# PERfECT-PRO-1.net
KiCad netlist of a schematic drawn in Altium Designer
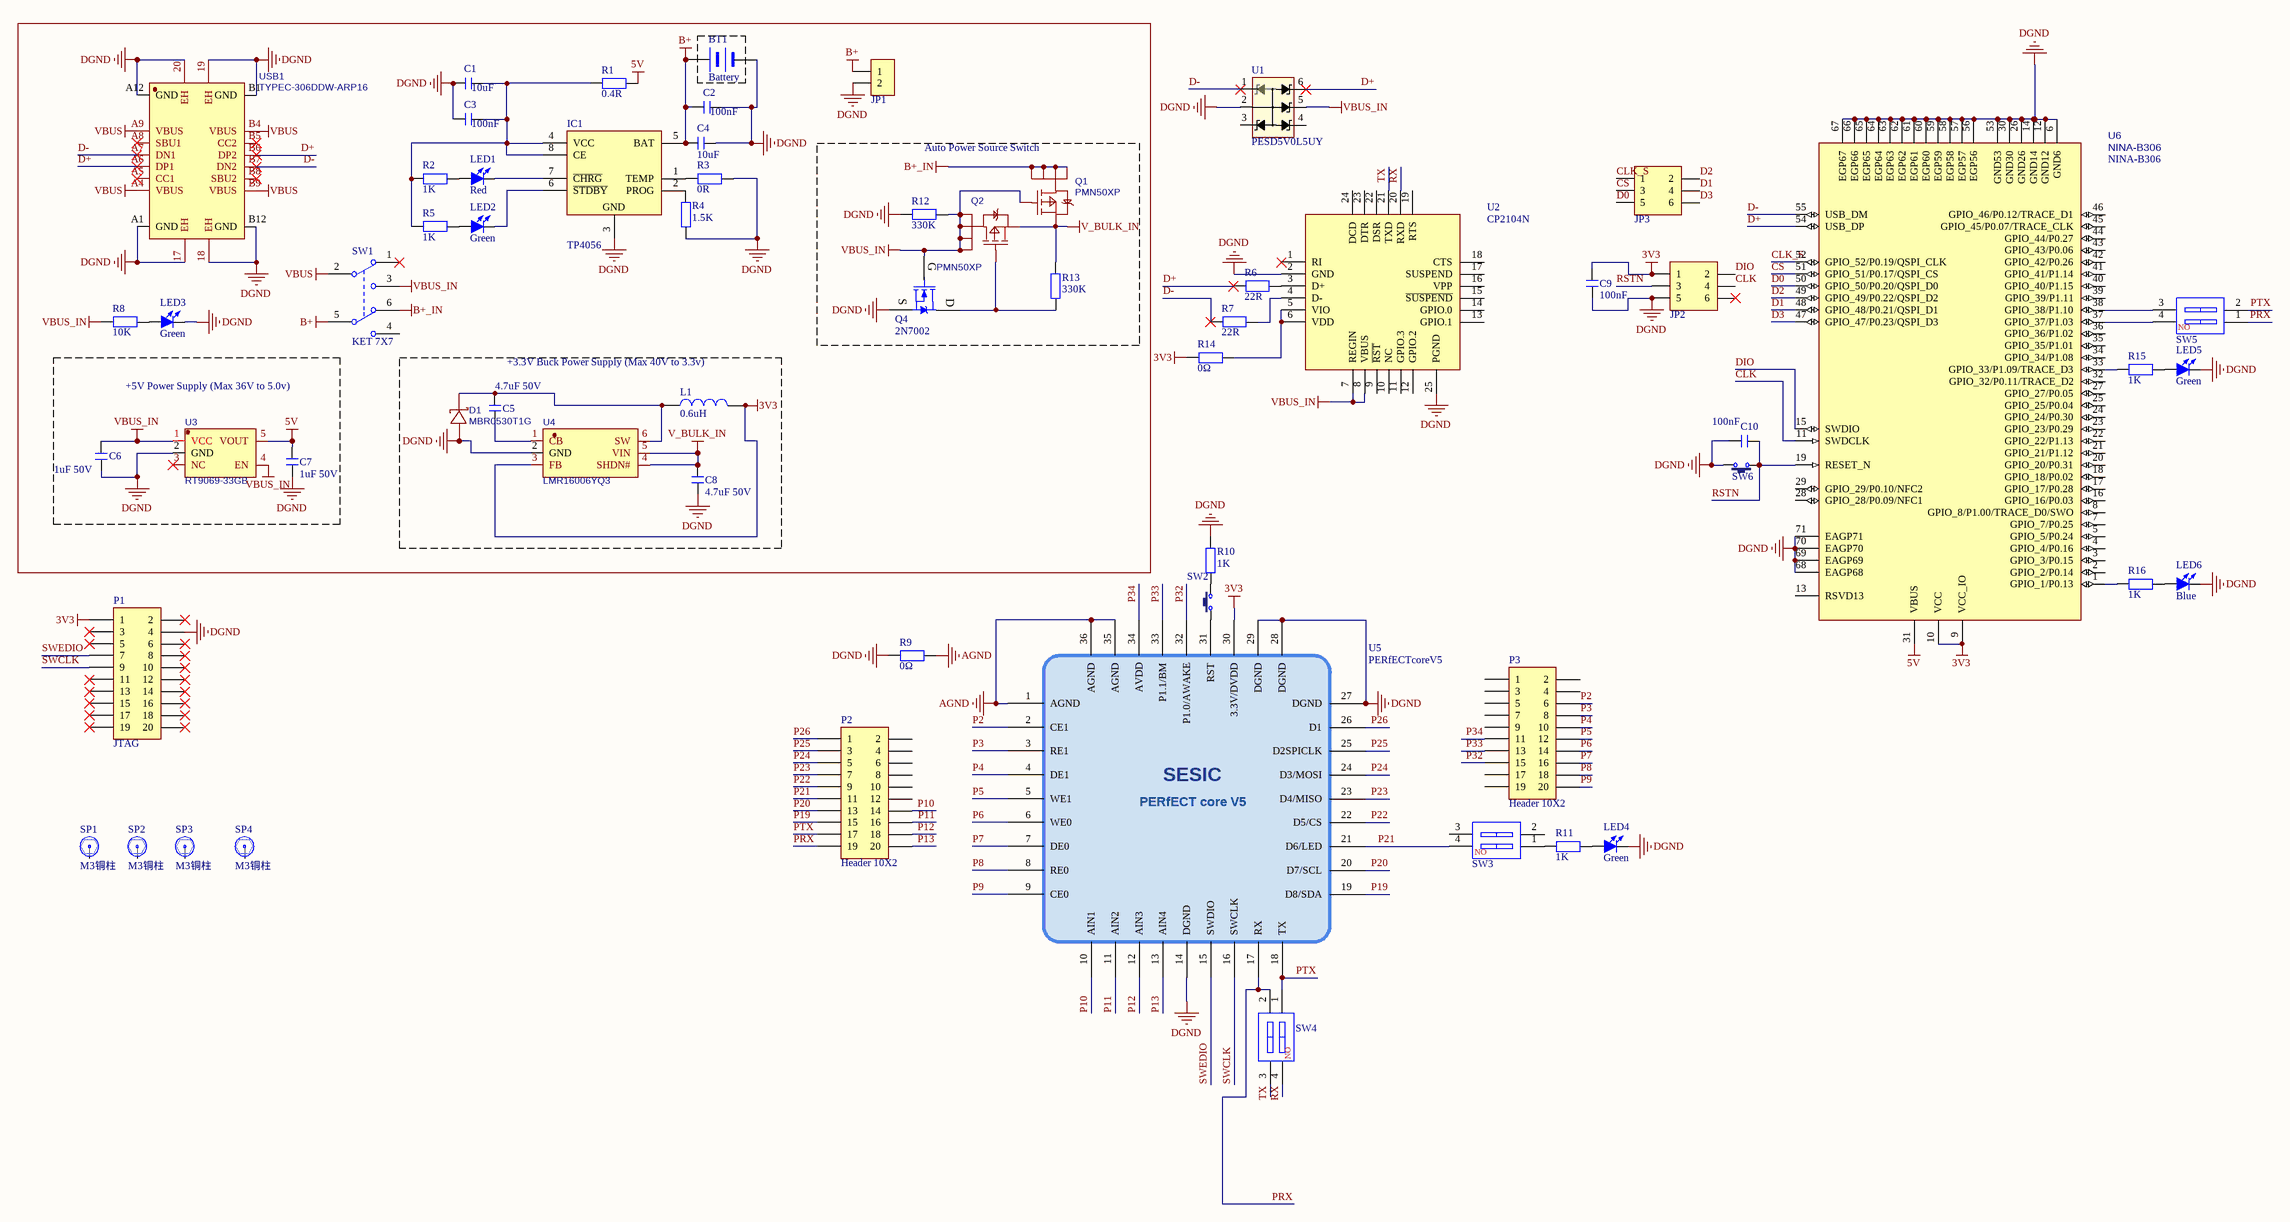
[diagram p0: PERfECT-PRO-1.SchDoc]

(export (version "E")
  (design (tool "Eeschema 10.0.6"))
  (components
    (comp (ref "BT1") (value "Battery") (libsource (lib "电池及电源") (part "干电池")))
    (comp (ref "C1")
      (value "10uF")
      (footprint "C 0603_L")
      (description "无极性贴片电容")
      (fields (field (name "版权归属") "源创客"))
      (libsource (lib "3.1   - 电阻-电容-电感") (part "C"))
    )
    (comp (ref "C2")
      (value "100nF")
      (footprint "C 0603_L")
      (description "无极性贴片电容")
      (fields (field (name "版权归属") "源创客"))
      (libsource (lib "3.1   - 电阻-电容-电感") (part "C"))
    )
    (comp (ref "C3")
      (value "100nF")
      (footprint "C 0603_L")
      (description "无极性贴片电容")
      (fields (field (name "版权归属") "源创客"))
      (libsource (lib "3.1   - 电阻-电容-电感") (part "C"))
    )
    (comp (ref "C4")
      (value "10uF")
      (footprint "C 0603_L")
      (description "无极性贴片电容")
      (fields (field (name "版权归属") "源创客"))
      (libsource (lib "3.1   - 电阻-电容-电感") (part "C"))
    )
    (comp (ref "C5")
      (value "4.7uF 50V")
      (footprint "C 0603_L")
      (description "无极性贴片电容")
      (fields (field (name "版权归属") "源创客"))
      (libsource (lib "3.1   - 电阻-电容-电感") (part "C"))
    )
    (comp (ref "C6")
      (value "1uF 50V")
      (footprint "C 0603_L")
      (description "无极性贴片电容")
      (fields (field (name "版权归属") "源创客"))
      (libsource (lib "3.1   - 电阻-电容-电感") (part "C"))
    )
    (comp (ref "C7")
      (value "1uF 50V")
      (footprint "C 0603_L")
      (description "无极性贴片电容")
      (fields (field (name "版权归属") "源创客"))
      (libsource (lib "3.1   - 电阻-电容-电感") (part "C"))
    )
    (comp (ref "C8")
      (value "4.7uF 50V")
      (footprint "C 0603_L")
      (description "无极性贴片电容")
      (fields (field (name "版权归属") "源创客"))
      (libsource (lib "3.1   - 电阻-电容-电感") (part "C"))
    )
    (comp (ref "C9")
      (value "100nF")
      (footprint "C 0603_L")
      (description "无极性贴片电容")
      (fields (field (name "版权归属") "源创客"))
      (libsource (lib "3.1   - 电阻-电容-电感") (part "C"))
    )
    (comp (ref "C10")
      (value "100nF")
      (footprint "C 0603_L")
      (description "无极性贴片电容")
      (fields (field (name "版权归属") "源创客"))
      (libsource (lib "3.1   - 电阻-电容-电感") (part "C"))
    )
    (comp (ref "D1")
      (value "MBR0530T1G")
      (footprint "MBR0530T1G")
      (fields (field (name "BOM_SUPPLIER PART") "C82046"))
      (libsource (lib "PERfECT-PRO") (part "MBR0530T1G"))
    )
    (comp (ref "IC1")
      (value "TP4056")
      (footprint "SOP8_N")
      (description "锂电池充电管理")
      (fields (field (name "版权归属") "源创客"))
      (libsource (lib "1.3   - 电源类芯片") (part "TP4056"))
    )
    (comp (ref "JP1")
      (value "HDR-1X2")
      (footprint "XH2.54-LI-2P")
      (description "2P接插件")
      (fields (field (name "版权归属") "源创客"))
      (libsource (lib "4.5   - 接插件-脚距2.54") (part "Header 2"))
    )
    (comp (ref "JP2")
      (value "Header3X2")
      (footprint "HDR2.54-LI-2x3P")
      (description "3*2P接插件")
      (fields (field (name "版权归属") "源创客"))
      (libsource (lib "4.5   - 接插件-脚距2.54") (part "Header 3X2"))
    )
    (comp (ref "JP3")
      (value "Header3X2")
      (footprint "HDR2.54-LI-2x3P")
      (description "3*2P接插件")
      (fields (field (name "版权归属") "源创客"))
      (libsource (lib "4.5   - 接插件-脚距2.54") (part "Header 3X2"))
    )
    (comp (ref "L1")
      (value "0.6uH")
      (footprint "L 1206")
      (description "小功率贴片电感")
      (fields (field (name "版权归属") "源创客"))
      (libsource (lib "3.1   - 电阻-电容-电感") (part "L"))
    )
    (comp (ref "LED1")
      (value "Red")
      (footprint "LED 0603R")
      (description "贴片LED")
      (fields (field (name "版权归属") "源创客"))
      (libsource (lib "9.1   - LED") (part "LED-SMD"))
    )
    (comp (ref "LED2")
      (value "Green")
      (footprint "LED 0603R")
      (description "贴片LED")
      (fields (field (name "版权归属") "源创客"))
      (libsource (lib "9.1   - LED") (part "LED-SMD"))
    )
    (comp (ref "LED3")
      (value "Green")
      (footprint "LED 0603R")
      (description "贴片LED")
      (fields (field (name "版权归属") "源创客"))
      (libsource (lib "9.1   - LED") (part "LED-SMD"))
    )
    (comp (ref "LED4")
      (value "Green")
      (footprint "LED 0603R")
      (description "贴片LED")
      (fields (field (name "版权归属") "源创客"))
      (libsource (lib "9.1   - LED") (part "LED-SMD"))
    )
    (comp (ref "LED5")
      (value "Green")
      (footprint "LED 0603R")
      (description "贴片LED")
      (fields (field (name "版权归属") "源创客"))
      (libsource (lib "9.1   - LED") (part "LED-SMD"))
    )
    (comp (ref "LED6")
      (value "Blue")
      (footprint "LED 0603R")
      (description "贴片LED")
      (fields (field (name "版权归属") "源创客"))
      (libsource (lib "9.1   - LED") (part "LED-SMD"))
    )
    (comp (ref "P1")
      (value "JTAG")
      (footprint "HDR2X10")
      (description "Header, 10-Pin, Dual row")
      (fields (field (name "PUBLISHER") "Altium Limited"))
      (libsource (lib "PERfECT-PRO") (part "Header 10X2"))
    )
    (comp (ref "P2")
      (value "Header 10X2")
      (footprint "HDR2X10")
      (description "Header, 10-Pin, Dual row")
      (fields (field (name "PUBLISHER") "Altium Limited"))
      (libsource (lib "PERfECT-PRO") (part "Header 10X2"))
    )
    (comp (ref "P3")
      (value "Header 10X2")
      (footprint "HDR2X10")
      (description "Header, 10-Pin, Dual row")
      (fields (field (name "PUBLISHER") "Altium Limited"))
      (libsource (lib "PERfECT-PRO") (part "Header 10X2"))
    )
    (comp (ref "Q1")
      (value "PMN50XP")
      (footprint "PMN50XP:PMN50XP")
      (fields (field (name "BOM_SUPPLIER PART") "C558228") (field (name "CONTRIBUTOR") "LCSC"))
      (libsource (lib "PERfECT-PRO-LIB") (part "PMN50XP"))
    )
    (comp (ref "Q2")
      (value "PMN50XP")
      (footprint "PMN50XP:PMN50XP")
      (fields (field (name "BOM_SUPPLIER PART") "C558228") (field (name "CONTRIBUTOR") "LCSC"))
      (libsource (lib "PERfECT-PRO-LIB") (part "PMN50XP"))
    )
    (comp (ref "Q4")
      (value "2N7002")
      (footprint "SOT23-3N")
      (description "N沟道场效应管")
      (fields (field (name "版权归属") "源创客"))
      (libsource (lib "6.1   - 场效应管-可控硅") (part "SI2302"))
    )
    (comp (ref "R1")
      (value "0.4R")
      (footprint "R 0603_L")
      (description "贴片电阻")
      (fields (field (name "版权归属") "源创客"))
      (libsource (lib "3.1   - 电阻-电容-电感") (part "R"))
    )
    (comp (ref "R2")
      (value "1K")
      (footprint "R 0603_L")
      (description "贴片电阻")
      (fields (field (name "版权归属") "源创客"))
      (libsource (lib "3.1   - 电阻-电容-电感") (part "R"))
    )
    (comp (ref "R3")
      (value "0R")
      (footprint "R 0603_L")
      (description "贴片电阻")
      (fields (field (name "版权归属") "源创客"))
      (libsource (lib "3.1   - 电阻-电容-电感") (part "R"))
    )
    (comp (ref "R4")
      (value "1.5K")
      (footprint "R 0603_L")
      (description "贴片电阻")
      (fields (field (name "版权归属") "源创客"))
      (libsource (lib "3.1   - 电阻-电容-电感") (part "R"))
    )
    (comp (ref "R5")
      (value "1K")
      (footprint "R 0603_L")
      (description "贴片电阻")
      (fields (field (name "版权归属") "源创客"))
      (libsource (lib "3.1   - 电阻-电容-电感") (part "R"))
    )
    (comp (ref "R6")
      (value "22R")
      (footprint "R 0603_L")
      (description "贴片电阻")
      (fields (field (name "版权归属") "源创客"))
      (libsource (lib "3.1   - 电阻-电容-电感") (part "R"))
    )
    (comp (ref "R7")
      (value "22R")
      (footprint "R 0603_L")
      (description "贴片电阻")
      (fields (field (name "版权归属") "源创客"))
      (libsource (lib "3.1   - 电阻-电容-电感") (part "R"))
    )
    (comp (ref "R8")
      (value "10K")
      (footprint "R 0603_L")
      (description "贴片电阻")
      (fields (field (name "版权归属") "源创客"))
      (libsource (lib "3.1   - 电阻-电容-电感") (part "R"))
    )
    (comp (ref "R9")
      (value "0Ω")
      (footprint "R 0603_L")
      (description "贴片电阻")
      (fields (field (name "版权归属") "源创客"))
      (libsource (lib "3.1   - 电阻-电容-电感") (part "R"))
    )
    (comp (ref "R10")
      (value "1K")
      (footprint "R 0603_L")
      (description "贴片电阻")
      (fields (field (name "版权归属") "源创客"))
      (libsource (lib "3.1   - 电阻-电容-电感") (part "R"))
    )
    (comp (ref "R11")
      (value "1K")
      (footprint "R 0603_L")
      (description "贴片电阻")
      (fields (field (name "版权归属") "源创客"))
      (libsource (lib "3.1   - 电阻-电容-电感") (part "R"))
    )
    (comp (ref "R12")
      (value "330K")
      (footprint "R 0603_L")
      (description "贴片电阻")
      (fields (field (name "版权归属") "源创客"))
      (libsource (lib "3.1   - 电阻-电容-电感") (part "R"))
    )
    (comp (ref "R13")
      (value "330K")
      (footprint "R 0603_L")
      (description "贴片电阻")
      (fields (field (name "版权归属") "源创客"))
      (libsource (lib "3.1   - 电阻-电容-电感") (part "R"))
    )
    (comp (ref "R14")
      (value "0Ω")
      (footprint "R 0603_L")
      (description "贴片电阻")
      (fields (field (name "版权归属") "源创客"))
      (libsource (lib "3.1   - 电阻-电容-电感") (part "R"))
    )
    (comp (ref "R15")
      (value "1K")
      (footprint "R 0603_L")
      (description "贴片电阻")
      (fields (field (name "版权归属") "源创客"))
      (libsource (lib "3.1   - 电阻-电容-电感") (part "R"))
    )
    (comp (ref "R16")
      (value "1K")
      (footprint "R 0603_L")
      (description "贴片电阻")
      (fields (field (name "版权归属") "源创客"))
      (libsource (lib "3.1   - 电阻-电容-电感") (part "R"))
    )
    (comp (ref "SP1")
      (value "M3铜柱")
      (footprint "M3x4_L")
      (description "铜柱")
      (fields (field (name "版权归属") "源创客"))
      (libsource (lib "15.1 - 未分类器件") (part "铜柱小焊盘"))
    )
    (comp (ref "SP2")
      (value "M3铜柱")
      (footprint "M3x4_L")
      (description "铜柱")
      (fields (field (name "版权归属") "源创客"))
      (libsource (lib "15.1 - 未分类器件") (part "铜柱小焊盘"))
    )
    (comp (ref "SP3")
      (value "M3铜柱")
      (footprint "M3x4_L")
      (description "铜柱")
      (fields (field (name "版权归属") "源创客"))
      (libsource (lib "15.1 - 未分类器件") (part "铜柱小焊盘"))
    )
    (comp (ref "SP4")
      (value "M3铜柱")
      (footprint "M3x4_L")
      (description "铜柱")
      (fields (field (name "版权归属") "源创客"))
      (libsource (lib "15.1 - 未分类器件") (part "铜柱小焊盘"))
    )
    (comp (ref "SW1")
      (value "KET 7X7")
      (footprint "KFT DIP-7X7")
      (description "7*7自锁开关")
      (fields (field (name "版权归属") "源创客"))
      (libsource (lib "5.1   - 按键-开关") (part "KET 7X7"))
    )
    (comp (ref "SW2")
      (value "3x6x5")
      (footprint "TSW SMD-3*6*2.5")
      (description "3x6轻触开关")
      (fields (field (name "版权归属") "源创客"))
      (libsource (lib "5.1   - 按键-开关") (part "TSW 3x6"))
    )
    (comp (ref "SW3")
      (value "CSW-2P")
      (footprint "CSW1.27 SMD-2P")
      (description "2路编码开关")
      (fields (field (name "版权归属") "源创客"))
      (libsource (lib "5.1   - 按键-开关") (part "CSW-2P"))
    )
    (comp (ref "SW4")
      (value "CSW-2P")
      (footprint "CSW1.27 SMD-2P")
      (description "2路编码开关")
      (fields (field (name "版权归属") "源创客"))
      (libsource (lib "5.1   - 按键-开关") (part "CSW-2P"))
    )
    (comp (ref "SW5")
      (value "CSW-2P")
      (footprint "CSW1.27 SMD-2P")
      (description "2路编码开关")
      (fields (field (name "版权归属") "源创客"))
      (libsource (lib "5.1   - 按键-开关") (part "CSW-2P"))
    )
    (comp (ref "SW6")
      (value "3x6x5")
      (footprint "TSW SMD-3*6*2.5")
      (description "3x6轻触开关")
      (fields (field (name "版权归属") "源创客"))
      (libsource (lib "") (part "TSW 3x6_1"))
    )
    (comp (ref "U1")
      (value "PESD5V0L5UY")
      (footprint "SOT65P210X110-6N")
      (description "TVS SOT-363 RoHS")
      (fields (field (name "MANUFACTURER") "Yenji") (field (name "PARTNUMBER") "PESD5V0L5UY"))
      (libsource (lib "PERfECT-PRO") (part "PESD5V0L5UY"))
    )
    (comp (ref "U2")
      (value "CP2104N")
      (footprint "24-QFN")
      (description "IC BRIDGE USB TO UART 24QFN")
      (fields (field (name "MANUFACTURER") "Silicon Labs") (field (name "PARTNUMBER") "C47742"))
      (libsource (lib "PERfECT-PRO") (part "CP2104N"))
    )
    (comp (ref "U3")
      (value "RT9069-33GB")
      (footprint "SOT-23-5_L3.0-W1.7-P0.95-LS2.8-BR")
      (fields (field (name "BOM_SUPPLIER PART") "C147969") (field (name "CONTRIBUTOR") "LCSC"))
      (libsource (lib "PERfECT-PRO") (part "RT9069-33GB"))
    )
    (comp (ref "U4")
      (value "LMR16006YQ3")
      (footprint "LMR16006YQ3")
      (fields
        (field (name "BOM_SUPPLIER PART") "C290195")
        (field (name "BOM_MANUFACTURER PART") "LMR16006YDDCR")
        (field (name "CONTRIBUTOR") "LCSC")
      )
      (libsource (lib "PERfECT-PRO") (part "LMR16006YQ3"))
    )
    (comp (ref "U5")
      (value "PERfECTcoreV5")
      (footprint "PERfECTcore36")
      (description "This is the 5th version of PERfEC core.https://github.com/WISE-PERfECT/PERfECT")
      (libsource (lib "PERfECT-PRO") (part "PERfECTcoreV5"))
    )
    (comp (ref "U6")
      (value "NINA-B306")
      (footprint "NINA_LGA71R_1500X1000X223_PCB")
      (description "u-blox NINA-B306 Bluetooth 5 LE, 802.15.4 module")
      (fields (field (name "MANUFACTURER") "u-blox") (field (name "ALTIUM_VALUE") "NINA-B306"))
      (libsource (lib "PERfECT-PRO") (part "NINA-B306"))
    )
    (comp (ref "USB1")
      (value "TYPEC-306DDW-ARP16")
      (footprint "USBC_DIP")
      (fields (field (name "BOM_SUPPLIER PART") "C2840393") (field (name "CONTRIBUTOR") "LCSC"))
      (libsource (lib "PERfECT-PRO") (part "TYPEC-306DDW-ARP16"))
    )
  )
  (nets
    (net (code "1") (name "/CLK") (class "Default")
      (node (ref "JP2") (pin "4") (pinfunction "4_4") (pintype "passive"))
      (node (ref "U6") (pin "11") (pinfunction "SWDCLK_11") (pintype "input"))
    )
    (net (code "2") (name "/CLK_S") (class "Default")
      (node (ref "JP3") (pin "1") (pinfunction "1_1") (pintype "passive"))
      (node (ref "U6") (pin "52") (pinfunction "GPIO_52/P0.19/QSPI_CLK_52") (pintype "bidirectional"))
    )
    (net (code "3") (name "/CS") (class "Default")
      (node (ref "JP3") (pin "3") (pinfunction "3_3") (pintype "passive"))
      (node (ref "U6") (pin "51") (pinfunction "GPIO_51/P0.17/QSPI_CS_51") (pintype "bidirectional"))
    )
    (net (code "4") (name "/D+") (class "Default")
      (node (ref "R6") (pin "1") (pinfunction "1_1") (pintype "passive"))
      (node (ref "U1") (pin "6") (pinfunction "6_6") (pintype "passive"))
      (node (ref "U6") (pin "54") (pinfunction "USB_DP_54") (pintype "bidirectional"))
      (node (ref "USB1") (pin "A6") (pinfunction "DP1_A6") (pintype "passive"))
      (node (ref "USB1") (pin "B6") (pinfunction "DP2_B6") (pintype "passive"))
    )
    (net (code "5") (name "/D-") (class "Default")
      (node (ref "R7") (pin "1") (pinfunction "1_1") (pintype "passive"))
      (node (ref "U1") (pin "1") (pinfunction "1_1") (pintype "passive"))
      (node (ref "U6") (pin "55") (pinfunction "USB_DM_55") (pintype "bidirectional"))
      (node (ref "USB1") (pin "A7") (pinfunction "DN1_A7") (pintype "passive"))
      (node (ref "USB1") (pin "B7") (pinfunction "DN2_B7") (pintype "passive"))
    )
    (net (code "6") (name "/D0") (class "Default")
      (node (ref "JP3") (pin "5") (pinfunction "5_5") (pintype "passive"))
      (node (ref "U6") (pin "50") (pinfunction "GPIO_50/P0.20/QSPI_D0_50") (pintype "bidirectional"))
    )
    (net (code "7") (name "/D1") (class "Default")
      (node (ref "JP3") (pin "4") (pinfunction "4_4") (pintype "passive"))
      (node (ref "U6") (pin "48") (pinfunction "GPIO_48/P0.21/QSPI_D1_48") (pintype "bidirectional"))
    )
    (net (code "8") (name "/D2") (class "Default")
      (node (ref "JP3") (pin "2") (pinfunction "2_2") (pintype "passive"))
      (node (ref "U6") (pin "49") (pinfunction "GPIO_49/P0.22/QSPI_D2_49") (pintype "bidirectional"))
    )
    (net (code "9") (name "/D3") (class "Default")
      (node (ref "JP3") (pin "6") (pinfunction "6_6") (pintype "passive"))
      (node (ref "U6") (pin "47") (pinfunction "GPIO_47/P0.23/QSPI_D3_47") (pintype "bidirectional"))
    )
    (net (code "10") (name "/DIO") (class "Default")
      (node (ref "JP2") (pin "2") (pinfunction "2_2") (pintype "passive"))
      (node (ref "U6") (pin "15") (pinfunction "SWDIO_15") (pintype "bidirectional"))
    )
    (net (code "11") (name "/P2") (class "Default")
      (node (ref "P3") (pin "6") (pinfunction "6_6") (pintype "passive"))
      (node (ref "U5") (pin "2") (pinfunction "CE1_2") (pintype "passive"))
    )
    (net (code "12") (name "/P3") (class "Default")
      (node (ref "P3") (pin "8") (pinfunction "8_8") (pintype "passive"))
      (node (ref "U5") (pin "3") (pinfunction "RE1_3") (pintype "passive"))
    )
    (net (code "13") (name "/P4") (class "Default")
      (node (ref "P3") (pin "10") (pinfunction "10_10") (pintype "passive"))
      (node (ref "U5") (pin "4") (pinfunction "DE1_4") (pintype "passive"))
    )
    (net (code "14") (name "/P5") (class "Default")
      (node (ref "P3") (pin "12") (pinfunction "12_12") (pintype "passive"))
      (node (ref "U5") (pin "5") (pinfunction "WE1_5") (pintype "passive"))
    )
    (net (code "15") (name "/P6") (class "Default")
      (node (ref "P3") (pin "14") (pinfunction "14_14") (pintype "passive"))
      (node (ref "U5") (pin "6") (pinfunction "WE0_6") (pintype "passive"))
    )
    (net (code "16") (name "/P7") (class "Default")
      (node (ref "P3") (pin "16") (pinfunction "16_16") (pintype "passive"))
      (node (ref "U5") (pin "7") (pinfunction "DE0_7") (pintype "passive"))
    )
    (net (code "17") (name "/P8") (class "Default")
      (node (ref "P3") (pin "18") (pinfunction "18_18") (pintype "passive"))
      (node (ref "U5") (pin "8") (pinfunction "RE0_8") (pintype "passive"))
    )
    (net (code "18") (name "/P9") (class "Default")
      (node (ref "P3") (pin "20") (pinfunction "20_20") (pintype "passive"))
      (node (ref "U5") (pin "9") (pinfunction "CE0_9") (pintype "passive"))
    )
    (net (code "19") (name "/P10") (class "Default")
      (node (ref "P2") (pin "14") (pinfunction "14_14") (pintype "passive"))
      (node (ref "U5") (pin "10") (pinfunction "AIN1_10") (pintype "passive"))
    )
    (net (code "20") (name "/P11") (class "Default")
      (node (ref "P2") (pin "16") (pinfunction "16_16") (pintype "passive"))
      (node (ref "U5") (pin "11") (pinfunction "AIN2_11") (pintype "passive"))
    )
    (net (code "21") (name "/P12") (class "Default")
      (node (ref "P2") (pin "18") (pinfunction "18_18") (pintype "passive"))
      (node (ref "U5") (pin "12") (pinfunction "AIN3_12") (pintype "passive"))
    )
    (net (code "22") (name "/P13") (class "Default")
      (node (ref "P2") (pin "20") (pinfunction "20_20") (pintype "passive"))
      (node (ref "U5") (pin "13") (pinfunction "AIN4_13") (pintype "passive"))
    )
    (net (code "23") (name "/P19") (class "Default")
      (node (ref "P2") (pin "15") (pinfunction "15_15") (pintype "passive"))
      (node (ref "U5") (pin "19") (pinfunction "D8/SDA_19") (pintype "passive"))
    )
    (net (code "24") (name "/P20") (class "Default")
      (node (ref "P2") (pin "13") (pinfunction "13_13") (pintype "passive"))
      (node (ref "U5") (pin "20") (pinfunction "D7/SCL_20") (pintype "passive"))
    )
    (net (code "25") (name "/P21") (class "Default")
      (node (ref "P2") (pin "11") (pinfunction "11_11") (pintype "passive"))
      (node (ref "SW3") (pin "4") (pinfunction "4_4") (pintype "passive"))
      (node (ref "U5") (pin "21") (pinfunction "D6/LED_21") (pintype "passive"))
    )
    (net (code "26") (name "/P22") (class "Default")
      (node (ref "P2") (pin "9") (pinfunction "9_9") (pintype "passive"))
      (node (ref "U5") (pin "22") (pinfunction "D5/CS_22") (pintype "passive"))
    )
    (net (code "27") (name "/P23") (class "Default")
      (node (ref "P2") (pin "7") (pinfunction "7_7") (pintype "passive"))
      (node (ref "U5") (pin "23") (pinfunction "D4/MISO_23") (pintype "passive"))
    )
    (net (code "28") (name "/P24") (class "Default")
      (node (ref "P2") (pin "5") (pinfunction "5_5") (pintype "passive"))
      (node (ref "U5") (pin "24") (pinfunction "D3/MOSI_24") (pintype "passive"))
    )
    (net (code "29") (name "/P25") (class "Default")
      (node (ref "P2") (pin "3") (pinfunction "3_3") (pintype "passive"))
      (node (ref "U5") (pin "25") (pinfunction "D2SPICLK_25") (pintype "passive"))
    )
    (net (code "30") (name "/P26") (class "Default")
      (node (ref "P2") (pin "1") (pinfunction "1_1") (pintype "passive"))
      (node (ref "U5") (pin "26") (pinfunction "D1_26") (pintype "passive"))
    )
    (net (code "31") (name "/P32") (class "Default")
      (node (ref "P3") (pin "15") (pinfunction "15_15") (pintype "passive"))
      (node (ref "U5") (pin "32") (pinfunction "P1.0/AWAKE_32") (pintype "passive"))
    )
    (net (code "32") (name "/P33") (class "Default")
      (node (ref "P3") (pin "13") (pinfunction "13_13") (pintype "passive"))
      (node (ref "U5") (pin "33") (pinfunction "P1.1/BM_33") (pintype "passive"))
    )
    (net (code "33") (name "/P34") (class "Default")
      (node (ref "P3") (pin "11") (pinfunction "11_11") (pintype "passive"))
      (node (ref "U5") (pin "34") (pinfunction "AVDD_34") (pintype "passive"))
    )
    (net (code "34") (name "/PRX") (class "Default")
      (node (ref "P2") (pin "19") (pinfunction "19_19") (pintype "passive"))
      (node (ref "SW4") (pin "2") (pinfunction "2_2") (pintype "passive"))
      (node (ref "SW5") (pin "1") (pinfunction "1_1") (pintype "passive"))
      (node (ref "U5") (pin "17") (pinfunction "RX_17") (pintype "passive"))
    )
    (net (code "35") (name "/PTX") (class "Default")
      (node (ref "P2") (pin "17") (pinfunction "17_17") (pintype "passive"))
      (node (ref "SW4") (pin "1") (pinfunction "1_1") (pintype "passive"))
      (node (ref "SW5") (pin "2") (pinfunction "2_2") (pintype "passive"))
      (node (ref "U5") (pin "18") (pinfunction "TX_18") (pintype "passive"))
    )
    (net (code "36") (name "/RSTN") (class "Default")
      (node (ref "C10") (pin "2") (pinfunction "2_2") (pintype "passive"))
      (node (ref "JP2") (pin "3") (pinfunction "3_3") (pintype "passive"))
      (node (ref "SW6") (pin "1") (pinfunction "1_1") (pintype "passive"))
      (node (ref "U6") (pin "19") (pinfunction "RESET_N_19") (pintype "input"))
    )
    (net (code "37") (name "/RX") (class "Default")
      (node (ref "SW4") (pin "4") (pinfunction "4_4") (pintype "passive"))
      (node (ref "U2") (pin "20") (pinfunction "RXD_20") (pintype "passive"))
    )
    (net (code "38") (name "/SWCLK") (class "Default")
      (node (ref "P1") (pin "9") (pinfunction "9_9") (pintype "passive"))
      (node (ref "U5") (pin "16") (pinfunction "SWCLK_16") (pintype "passive"))
    )
    (net (code "39") (name "/SWEDIO") (class "Default")
      (node (ref "P1") (pin "7") (pinfunction "7_7") (pintype "passive"))
      (node (ref "U5") (pin "15") (pinfunction "SWDIO_15") (pintype "passive"))
    )
    (net (code "40") (name "/TX") (class "Default")
      (node (ref "SW4") (pin "3") (pinfunction "3_3") (pintype "passive"))
      (node (ref "U2") (pin "21") (pinfunction "TXD_21") (pintype "passive"))
    )
    (net (code "41") (name "3V3") (class "Default")
      (node (ref "C9") (pin "2") (pinfunction "2_2") (pintype "passive"))
      (node (ref "JP2") (pin "1") (pinfunction "1_1") (pintype "passive"))
      (node (ref "L1") (pin "2") (pinfunction "2_2") (pintype "passive"))
      (node (ref "P1") (pin "1") (pinfunction "1_1") (pintype "passive"))
      (node (ref "R14") (pin "1") (pinfunction "1_1") (pintype "passive"))
      (node (ref "U4") (pin "3") (pinfunction "FB_3") (pintype "passive"))
      (node (ref "U5") (pin "30") (pinfunction "3.3V/DVDD_30") (pintype "passive"))
      (node (ref "U6") (pin "10") (pinfunction "VCC_10") (pintype "power_in"))
      (node (ref "U6") (pin "9") (pinfunction "VCC_IO_9") (pintype "power_in"))
    )
    (net (code "42") (name "5V") (class "Default")
      (node (ref "C7") (pin "1") (pinfunction "1_1") (pintype "passive"))
      (node (ref "R1") (pin "2") (pinfunction "2_2") (pintype "passive"))
      (node (ref "U3") (pin "5") (pinfunction "VOUT_5") (pintype "passive"))
      (node (ref "U6") (pin "31") (pinfunction "VBUS_31") (pintype "power_in"))
    )
    (net (code "43") (name "AGND") (class "Default")
      (node (ref "R9") (pin "2") (pinfunction "2_2") (pintype "passive"))
      (node (ref "U5") (pin "1") (pinfunction "AGND_1") (pintype "passive"))
      (node (ref "U5") (pin "35") (pinfunction "AGND_35") (pintype "passive"))
      (node (ref "U5") (pin "36") (pinfunction "AGND_36") (pintype "passive"))
    )
    (net (code "44") (name "B+") (class "Default")
      (node (ref "BT1") (pin "1") (pinfunction "+_1") (pintype "passive"))
      (node (ref "C2") (pin "1") (pinfunction "1_1") (pintype "passive"))
      (node (ref "C4") (pin "1") (pinfunction "1_1") (pintype "passive"))
      (node (ref "IC1") (pin "5") (pinfunction "BAT_5") (pintype "passive"))
      (node (ref "JP1") (pin "1") (pinfunction "1_1") (pintype "passive"))
      (node (ref "SW1") (pin "5") (pinfunction "COM2_5") (pintype "passive"))
    )
    (net (code "45") (name "B+_IN") (class "Default")
      (node (ref "Q1") (pin "1") (pinfunction "D_1") (pintype "passive"))
      (node (ref "Q1") (pin "2") (pinfunction "D_2") (pintype "passive"))
      (node (ref "Q1") (pin "5") (pinfunction "D_5") (pintype "passive"))
      (node (ref "Q1") (pin "6") (pinfunction "D_6") (pintype "passive"))
      (node (ref "SW1") (pin "6") (pinfunction "NC2_6") (pintype "passive"))
    )
    (net (code "46") (name "DGND") (class "Default")
      (node (ref "BT1") (pin "2") (pinfunction "-_2") (pintype "passive"))
      (node (ref "C1") (pin "1") (pinfunction "1_1") (pintype "passive"))
      (node (ref "C10") (pin "1") (pinfunction "1_1") (pintype "passive"))
      (node (ref "C2") (pin "2") (pinfunction "2_2") (pintype "passive"))
      (node (ref "C3") (pin "1") (pinfunction "1_1") (pintype "passive"))
      (node (ref "C4") (pin "2") (pinfunction "2_2") (pintype "passive"))
      (node (ref "C6") (pin "1") (pinfunction "1_1") (pintype "passive"))
      (node (ref "C7") (pin "2") (pinfunction "2_2") (pintype "passive"))
      (node (ref "C8") (pin "2") (pinfunction "2_2") (pintype "passive"))
      (node (ref "C9") (pin "1") (pinfunction "1_1") (pintype "passive"))
      (node (ref "D1") (pin "2") (pinfunction "A_2") (pintype "passive"))
      (node (ref "IC1") (pin "3") (pinfunction "GND_3") (pintype "passive"))
      (node (ref "JP1") (pin "2") (pinfunction "2_2") (pintype "passive"))
      (node (ref "JP2") (pin "5") (pinfunction "5_5") (pintype "passive"))
      (node (ref "LED3") (pin "2") (pinfunction "K_2") (pintype "passive"))
      (node (ref "LED4") (pin "2") (pinfunction "K_2") (pintype "passive"))
      (node (ref "LED5") (pin "2") (pinfunction "K_2") (pintype "passive"))
      (node (ref "LED6") (pin "2") (pinfunction "K_2") (pintype "passive"))
      (node (ref "P1") (pin "4") (pinfunction "4_4") (pintype "passive"))
      (node (ref "Q4") (pin "2") (pinfunction "S_2") (pintype "passive"))
      (node (ref "R10") (pin "2") (pinfunction "2_2") (pintype "passive"))
      (node (ref "R12") (pin "1") (pinfunction "1_1") (pintype "passive"))
      (node (ref "R3") (pin "2") (pinfunction "2_2") (pintype "passive"))
      (node (ref "R4") (pin "1") (pinfunction "1_1") (pintype "passive"))
      (node (ref "R9") (pin "1") (pinfunction "1_1") (pintype "passive"))
      (node (ref "SW6") (pin "2") (pinfunction "2_2") (pintype "passive"))
      (node (ref "U1") (pin "2") (pinfunction "2_2") (pintype "passive"))
      (node (ref "U2") (pin "2") (pinfunction "GND_2") (pintype "power_in"))
      (node (ref "U2") (pin "25") (pinfunction "PGND_25") (pintype "passive"))
      (node (ref "U3") (pin "2") (pinfunction "GND_2") (pintype "passive"))
      (node (ref "U4") (pin "2") (pinfunction "GND_2") (pintype "passive"))
      (node (ref "U5") (pin "14") (pinfunction "DGND_14") (pintype "passive"))
      (node (ref "U5") (pin "27") (pinfunction "DGND_27") (pintype "passive"))
      (node (ref "U5") (pin "28") (pinfunction "DGND_28") (pintype "power_in"))
      (node (ref "U5") (pin "29") (pinfunction "DGND_29") (pintype "passive"))
      (node (ref "U6") (pin "12") (pinfunction "GND12_12") (pintype "power_in"))
      (node (ref "U6") (pin "14") (pinfunction "GND14_14") (pintype "power_in"))
      (node (ref "U6") (pin "26") (pinfunction "GND26_26") (pintype "power_in"))
      (node (ref "U6") (pin "30") (pinfunction "GND30_30") (pintype "power_in"))
      (node (ref "U6") (pin "53") (pinfunction "GND53_53") (pintype "power_in"))
      (node (ref "U6") (pin "56") (pinfunction "EGP56_56") (pintype "power_in"))
      (node (ref "U6") (pin "57") (pinfunction "EGP57_57") (pintype "power_in"))
      (node (ref "U6") (pin "58") (pinfunction "EGP58_58") (pintype "power_in"))
      (node (ref "U6") (pin "59") (pinfunction "EGP59_59") (pintype "power_in"))
      (node (ref "U6") (pin "6") (pinfunction "GND6_6") (pintype "power_in"))
      (node (ref "U6") (pin "60") (pinfunction "EGP60_60") (pintype "power_in"))
      (node (ref "U6") (pin "61") (pinfunction "EGP61_61") (pintype "power_in"))
      (node (ref "U6") (pin "62") (pinfunction "EGP62_62") (pintype "power_in"))
      (node (ref "U6") (pin "63") (pinfunction "EGP63_63") (pintype "power_in"))
      (node (ref "U6") (pin "64") (pinfunction "EGP64_64") (pintype "power_in"))
      (node (ref "U6") (pin "65") (pinfunction "EGP65_65") (pintype "power_in"))
      (node (ref "U6") (pin "66") (pinfunction "EGP66_66") (pintype "power_in"))
      (node (ref "U6") (pin "67") (pinfunction "EGP67_67") (pintype "power_in"))
      (node (ref "U6") (pin "68") (pinfunction "EAGP68_68") (pintype "power_in"))
      (node (ref "U6") (pin "69") (pinfunction "EAGP69_69") (pintype "power_in"))
      (node (ref "U6") (pin "70") (pinfunction "EAGP70_70") (pintype "power_in"))
      (node (ref "U6") (pin "71") (pinfunction "EAGP71_71") (pintype "power_in"))
      (node (ref "USB1") (pin "17") (pinfunction "EH_17") (pintype "passive"))
      (node (ref "USB1") (pin "18") (pinfunction "EH_18") (pintype "passive"))
      (node (ref "USB1") (pin "19") (pinfunction "EH_19") (pintype "passive"))
      (node (ref "USB1") (pin "20") (pinfunction "EH_20") (pintype "passive"))
      (node (ref "USB1") (pin "A1") (pinfunction "GND_A1") (pintype "passive"))
      (node (ref "USB1") (pin "A12") (pinfunction "GND_A12") (pintype "passive"))
      (node (ref "USB1") (pin "B1") (pinfunction "GND_B1") (pintype "passive"))
      (node (ref "USB1") (pin "B12") (pinfunction "GND_B12") (pintype "passive"))
    )
    (net (code "47") (name "Net-(D1-C)") (class "Default")
      (node (ref "C5") (pin "1") (pinfunction "1_1") (pintype "passive"))
      (node (ref "D1") (pin "1") (pinfunction "C_1") (pintype "passive"))
      (node (ref "L1") (pin "1") (pinfunction "1_1") (pintype "passive"))
      (node (ref "U4") (pin "6") (pinfunction "SW_6") (pintype "passive"))
    )
    (net (code "48") (name "Net-(IC1-CE)") (class "Default")
      (node (ref "C1") (pin "2") (pinfunction "2_2") (pintype "passive"))
      (node (ref "C3") (pin "2") (pinfunction "2_2") (pintype "passive"))
      (node (ref "IC1") (pin "4") (pinfunction "VCC_4") (pintype "passive"))
      (node (ref "IC1") (pin "8") (pinfunction "CE_8") (pintype "passive"))
      (node (ref "R1") (pin "1") (pinfunction "1_1") (pintype "passive"))
      (node (ref "R2") (pin "1") (pinfunction "1_1") (pintype "passive"))
      (node (ref "R5") (pin "1") (pinfunction "1_1") (pintype "passive"))
    )
    (net (code "49") (name "Net-(IC1-PROG)") (class "Default")
      (node (ref "IC1") (pin "2") (pinfunction "PROG_2") (pintype "passive"))
      (node (ref "R4") (pin "2") (pinfunction "2_2") (pintype "passive"))
    )
    (net (code "50") (name "Net-(IC1-TEMP)") (class "Default")
      (node (ref "IC1") (pin "1") (pinfunction "TEMP_1") (pintype "passive"))
      (node (ref "R3") (pin "1") (pinfunction "1_1") (pintype "passive"))
    )
    (net (code "51") (name "Net-(IC1-~{CHRG})") (class "Default")
      (node (ref "IC1") (pin "7") (pinfunction "~{CHRG}_7") (pintype "passive"))
      (node (ref "LED1") (pin "2") (pinfunction "K_2") (pintype "passive"))
    )
    (net (code "52") (name "Net-(IC1-~{STDBY})") (class "Default")
      (node (ref "IC1") (pin "6") (pinfunction "~{STDBY}_6") (pintype "passive"))
      (node (ref "LED2") (pin "2") (pinfunction "K_2") (pintype "passive"))
    )
    (net (code "53") (name "Net-(LED1-A)") (class "Default")
      (node (ref "LED1") (pin "1") (pinfunction "A_1") (pintype "passive"))
      (node (ref "R2") (pin "2") (pinfunction "2_2") (pintype "passive"))
    )
    (net (code "54") (name "Net-(LED2-A)") (class "Default")
      (node (ref "LED2") (pin "1") (pinfunction "A_1") (pintype "passive"))
      (node (ref "R5") (pin "2") (pinfunction "2_2") (pintype "passive"))
    )
    (net (code "55") (name "Net-(LED3-A)") (class "Default")
      (node (ref "LED3") (pin "1") (pinfunction "A_1") (pintype "passive"))
      (node (ref "R8") (pin "2") (pinfunction "2_2") (pintype "passive"))
    )
    (net (code "56") (name "Net-(LED4-A)") (class "Default")
      (node (ref "LED4") (pin "1") (pinfunction "A_1") (pintype "passive"))
      (node (ref "R11") (pin "2") (pinfunction "2_2") (pintype "passive"))
    )
    (net (code "57") (name "Net-(LED5-A)") (class "Default")
      (node (ref "LED5") (pin "1") (pinfunction "A_1") (pintype "passive"))
      (node (ref "R15") (pin "2") (pinfunction "2_2") (pintype "passive"))
    )
    (net (code "58") (name "Net-(LED6-A)") (class "Default")
      (node (ref "LED6") (pin "1") (pinfunction "A_1") (pintype "passive"))
      (node (ref "R16") (pin "2") (pinfunction "2_2") (pintype "passive"))
    )
    (net (code "59") (name "Net-(Q2-G)") (class "Default")
      (node (ref "Q2") (pin "3") (pinfunction "G_3") (pintype "passive"))
      (node (ref "Q4") (pin "3") (pinfunction "D_3") (pintype "passive"))
      (node (ref "R13") (pin "1") (pinfunction "1_1") (pintype "passive"))
    )
    (net (code "60") (name "Net-(R10-Pad1)") (class "Default")
      (node (ref "R10") (pin "1") (pinfunction "1_1") (pintype "passive"))
      (node (ref "SW2") (pin "2") (pinfunction "2_2") (pintype "passive"))
    )
    (net (code "61") (name "Net-(R11-Pad1)") (class "Default")
      (node (ref "R11") (pin "1") (pinfunction "1_1") (pintype "passive"))
      (node (ref "SW3") (pin "1") (pinfunction "1_1") (pintype "passive"))
    )
    (net (code "62") (name "Net-(U2-D+)") (class "Default")
      (node (ref "R6") (pin "2") (pinfunction "2_2") (pintype "passive"))
      (node (ref "U2") (pin "3") (pinfunction "D+_3") (pintype "passive"))
    )
    (net (code "63") (name "Net-(U2-D-)") (class "Default")
      (node (ref "R7") (pin "2") (pinfunction "2_2") (pintype "passive"))
      (node (ref "U2") (pin "4") (pinfunction "D-_4") (pintype "passive"))
    )
    (net (code "64") (name "Net-(U2-VDD)") (class "Default")
      (node (ref "R14") (pin "2") (pinfunction "2_2") (pintype "passive"))
      (node (ref "U2") (pin "5") (pinfunction "VIO_5") (pintype "power_in"))
      (node (ref "U2") (pin "6") (pinfunction "VDD_6") (pintype "power_in"))
    )
    (net (code "65") (name "Net-(U4-CB)") (class "Default")
      (node (ref "C5") (pin "2") (pinfunction "2_2") (pintype "passive"))
      (node (ref "U4") (pin "1") (pinfunction "CB_1") (pintype "passive"))
    )
    (net (code "66") (name "Net-(U5-RST)") (class "Default")
      (node (ref "SW2") (pin "1") (pinfunction "1_1") (pintype "passive"))
      (node (ref "U5") (pin "31") (pinfunction "RST_31") (pintype "passive"))
    )
    (net (code "67") (name "Net-(U6-GPIO_1{slash}P0.13)") (class "Default")
      (node (ref "R16") (pin "1") (pinfunction "1_1") (pintype "passive"))
      (node (ref "U6") (pin "1") (pinfunction "GPIO_1/P0.13_1") (pintype "bidirectional"))
    )
    (net (code "68") (name "Net-(U6-GPIO_33{slash}P1.09{slash}TRACE_D3)") (class "Default")
      (node (ref "R15") (pin "1") (pinfunction "1_1") (pintype "passive"))
      (node (ref "U6") (pin "33") (pinfunction "GPIO_33/P1.09/TRACE_D3_33") (pintype "bidirectional"))
    )
    (net (code "69") (name "Net-(U6-GPIO_37{slash}P1.03)") (class "Default")
      (node (ref "SW5") (pin "4") (pinfunction "4_4") (pintype "passive"))
      (node (ref "U6") (pin "37") (pinfunction "GPIO_37/P1.03_37") (pintype "bidirectional"))
    )
    (net (code "70") (name "Net-(U6-GPIO_38{slash}P1.10)") (class "Default")
      (node (ref "SW5") (pin "3") (pinfunction "3_3") (pintype "passive"))
      (node (ref "U6") (pin "38") (pinfunction "GPIO_38/P1.10_38") (pintype "bidirectional"))
    )
    (net (code "71") (name "VBUS") (class "Default")
      (node (ref "SW1") (pin "2") (pinfunction "COM2_2") (pintype "passive"))
      (node (ref "USB1") (pin "A4") (pinfunction "VBUS_A4") (pintype "passive"))
      (node (ref "USB1") (pin "A9") (pinfunction "VBUS_A9") (pintype "passive"))
      (node (ref "USB1") (pin "B4") (pinfunction "VBUS_B4") (pintype "passive"))
      (node (ref "USB1") (pin "B9") (pinfunction "VBUS_B9") (pintype "passive"))
    )
    (net (code "72") (name "VBUS_IN") (class "Default")
      (node (ref "C6") (pin "2") (pinfunction "2_2") (pintype "passive"))
      (node (ref "Q1") (pin "3") (pinfunction "G_3") (pintype "passive"))
      (node (ref "Q2") (pin "1") (pinfunction "D_1") (pintype "passive"))
      (node (ref "Q2") (pin "2") (pinfunction "D_2") (pintype "passive"))
      (node (ref "Q2") (pin "5") (pinfunction "D_5") (pintype "passive"))
      (node (ref "Q2") (pin "6") (pinfunction "D_6") (pintype "passive"))
      (node (ref "Q4") (pin "1") (pinfunction "G_1") (pintype "passive"))
      (node (ref "R12") (pin "2") (pinfunction "2_2") (pintype "passive"))
      (node (ref "R8") (pin "1") (pinfunction "1_1") (pintype "passive"))
      (node (ref "SW1") (pin "3") (pinfunction "NO1_3") (pintype "passive"))
      (node (ref "U1") (pin "5") (pinfunction "5_5") (pintype "passive"))
      (node (ref "U2") (pin "7") (pinfunction "REGIN_7") (pintype "power_in"))
      (node (ref "U2") (pin "8") (pinfunction "VBUS_8") (pintype "power_in"))
      (node (ref "U3") (pin "1") (pinfunction "VCC_1") (pintype "passive"))
      (node (ref "U3") (pin "4") (pinfunction "EN_4") (pintype "passive"))
    )
    (net (code "73") (name "V_BULK_IN") (class "Default")
      (node (ref "C8") (pin "1") (pinfunction "1_1") (pintype "passive"))
      (node (ref "Q1") (pin "4") (pinfunction "S_4") (pintype "passive"))
      (node (ref "Q2") (pin "4") (pinfunction "S_4") (pintype "passive"))
      (node (ref "R13") (pin "2") (pinfunction "2_2") (pintype "passive"))
      (node (ref "U4") (pin "4") (pinfunction "SHDN#_4") (pintype "passive"))
      (node (ref "U4") (pin "5") (pinfunction "VIN_5") (pintype "passive"))
    )
    (net (code "74") (name "unconnected-(JP2-Pad6)") (class "Default")
      (node (ref "JP2") (pin "6") (pinfunction "6_6") (pintype "passive+no_connect"))
    )
    (net (code "75") (name "unconnected-(P1-Pad2)") (class "Default")
      (node (ref "P1") (pin "2") (pinfunction "2_2") (pintype "passive+no_connect"))
    )
    (net (code "76") (name "unconnected-(P1-Pad3)") (class "Default")
      (node (ref "P1") (pin "3") (pinfunction "3_3") (pintype "passive+no_connect"))
    )
    (net (code "77") (name "unconnected-(P1-Pad5)") (class "Default")
      (node (ref "P1") (pin "5") (pinfunction "5_5") (pintype "passive+no_connect"))
    )
    (net (code "78") (name "unconnected-(P1-Pad6)") (class "Default")
      (node (ref "P1") (pin "6") (pinfunction "6_6") (pintype "passive+no_connect"))
    )
    (net (code "79") (name "unconnected-(P1-Pad8)") (class "Default")
      (node (ref "P1") (pin "8") (pinfunction "8_8") (pintype "passive+no_connect"))
    )
    (net (code "80") (name "unconnected-(P1-Pad10)") (class "Default")
      (node (ref "P1") (pin "10") (pinfunction "10_10") (pintype "passive+no_connect"))
    )
    (net (code "81") (name "unconnected-(P1-Pad11)") (class "Default")
      (node (ref "P1") (pin "11") (pinfunction "11_11") (pintype "passive+no_connect"))
    )
    (net (code "82") (name "unconnected-(P1-Pad12)") (class "Default")
      (node (ref "P1") (pin "12") (pinfunction "12_12") (pintype "passive+no_connect"))
    )
    (net (code "83") (name "unconnected-(P1-Pad13)") (class "Default")
      (node (ref "P1") (pin "13") (pinfunction "13_13") (pintype "passive+no_connect"))
    )
    (net (code "84") (name "unconnected-(P1-Pad14)") (class "Default")
      (node (ref "P1") (pin "14") (pinfunction "14_14") (pintype "passive+no_connect"))
    )
    (net (code "85") (name "unconnected-(P1-Pad15)") (class "Default")
      (node (ref "P1") (pin "15") (pinfunction "15_15") (pintype "passive+no_connect"))
    )
    (net (code "86") (name "unconnected-(P1-Pad16)") (class "Default")
      (node (ref "P1") (pin "16") (pinfunction "16_16") (pintype "passive+no_connect"))
    )
    (net (code "87") (name "unconnected-(P1-Pad17)") (class "Default")
      (node (ref "P1") (pin "17") (pinfunction "17_17") (pintype "passive+no_connect"))
    )
    (net (code "88") (name "unconnected-(P1-Pad18)") (class "Default")
      (node (ref "P1") (pin "18") (pinfunction "18_18") (pintype "passive+no_connect"))
    )
    (net (code "89") (name "unconnected-(P1-Pad19)") (class "Default")
      (node (ref "P1") (pin "19") (pinfunction "19_19") (pintype "passive+no_connect"))
    )
    (net (code "90") (name "unconnected-(P1-Pad20)") (class "Default")
      (node (ref "P1") (pin "20") (pinfunction "20_20") (pintype "passive+no_connect"))
    )
    (net (code "91") (name "unconnected-(P2-Pad2)") (class "Default")
      (node (ref "P2") (pin "2") (pinfunction "2_2") (pintype "passive"))
    )
    (net (code "92") (name "unconnected-(P2-Pad4)") (class "Default")
      (node (ref "P2") (pin "4") (pinfunction "4_4") (pintype "passive"))
    )
    (net (code "93") (name "unconnected-(P2-Pad6)") (class "Default")
      (node (ref "P2") (pin "6") (pinfunction "6_6") (pintype "passive"))
    )
    (net (code "94") (name "unconnected-(P2-Pad8)") (class "Default")
      (node (ref "P2") (pin "8") (pinfunction "8_8") (pintype "passive"))
    )
    (net (code "95") (name "unconnected-(P2-Pad10)") (class "Default")
      (node (ref "P2") (pin "10") (pinfunction "10_10") (pintype "passive"))
    )
    (net (code "96") (name "unconnected-(P2-Pad12)") (class "Default")
      (node (ref "P2") (pin "12") (pinfunction "12_12") (pintype "passive"))
    )
    (net (code "97") (name "unconnected-(P3-Pad1)") (class "Default")
      (node (ref "P3") (pin "1") (pinfunction "1_1") (pintype "passive"))
    )
    (net (code "98") (name "unconnected-(P3-Pad2)") (class "Default")
      (node (ref "P3") (pin "2") (pinfunction "2_2") (pintype "passive"))
    )
    (net (code "99") (name "unconnected-(P3-Pad3)") (class "Default")
      (node (ref "P3") (pin "3") (pinfunction "3_3") (pintype "passive"))
    )
    (net (code "100") (name "unconnected-(P3-Pad4)") (class "Default")
      (node (ref "P3") (pin "4") (pinfunction "4_4") (pintype "passive"))
    )
    (net (code "101") (name "unconnected-(P3-Pad5)") (class "Default")
      (node (ref "P3") (pin "5") (pinfunction "5_5") (pintype "passive"))
    )
    (net (code "102") (name "unconnected-(P3-Pad7)") (class "Default")
      (node (ref "P3") (pin "7") (pinfunction "7_7") (pintype "passive"))
    )
    (net (code "103") (name "unconnected-(P3-Pad9)") (class "Default")
      (node (ref "P3") (pin "9") (pinfunction "9_9") (pintype "passive"))
    )
    (net (code "104") (name "unconnected-(P3-Pad17)") (class "Default")
      (node (ref "P3") (pin "17") (pinfunction "17_17") (pintype "passive"))
    )
    (net (code "105") (name "unconnected-(P3-Pad19)") (class "Default")
      (node (ref "P3") (pin "19") (pinfunction "19_19") (pintype "passive"))
    )
    (net (code "106") (name "unconnected-(SP1-Pad1)") (class "Default")
      (node (ref "SP1") (pin "1") (pinfunction "1_1") (pintype "passive"))
    )
    (net (code "107") (name "unconnected-(SP2-Pad1)") (class "Default")
      (node (ref "SP2") (pin "1") (pinfunction "1_1") (pintype "passive"))
    )
    (net (code "108") (name "unconnected-(SP3-Pad1)") (class "Default")
      (node (ref "SP3") (pin "1") (pinfunction "1_1") (pintype "passive"))
    )
    (net (code "109") (name "unconnected-(SP4-Pad1)") (class "Default")
      (node (ref "SP4") (pin "1") (pinfunction "1_1") (pintype "passive"))
    )
    (net (code "110") (name "unconnected-(SW1-NC1-Pad1)") (class "Default")
      (node (ref "SW1") (pin "1") (pinfunction "NC1_1") (pintype "passive+no_connect"))
    )
    (net (code "111") (name "unconnected-(SW1-NO2-Pad4)") (class "Default")
      (node (ref "SW1") (pin "4") (pinfunction "NO2_4") (pintype "passive"))
    )
    (net (code "112") (name "unconnected-(SW3-Pad2)") (class "Default")
      (node (ref "SW3") (pin "2") (pinfunction "2_2") (pintype "passive"))
    )
    (net (code "113") (name "unconnected-(SW3-Pad3)") (class "Default")
      (node (ref "SW3") (pin "3") (pinfunction "3_3") (pintype "passive"))
    )
    (net (code "114") (name "unconnected-(U1-Pad3)") (class "Default")
      (node (ref "U1") (pin "3") (pinfunction "3_3") (pintype "passive"))
    )
    (net (code "115") (name "unconnected-(U1-Pad4)") (class "Default")
      (node (ref "U1") (pin "4") (pinfunction "4_4") (pintype "passive"))
    )
    (net (code "116") (name "unconnected-(U2-CTS-Pad18)") (class "Default")
      (node (ref "U2") (pin "18") (pinfunction "CTS_18") (pintype "passive"))
    )
    (net (code "117") (name "unconnected-(U2-DCD-Pad24)") (class "Default")
      (node (ref "U2") (pin "24") (pinfunction "DCD_24") (pintype "passive"))
    )
    (net (code "118") (name "unconnected-(U2-DSR-Pad22)") (class "Default")
      (node (ref "U2") (pin "22") (pinfunction "DSR_22") (pintype "passive"))
    )
    (net (code "119") (name "unconnected-(U2-DTR-Pad23)") (class "Default")
      (node (ref "U2") (pin "23") (pinfunction "DTR_23") (pintype "passive"))
    )
    (net (code "120") (name "unconnected-(U2-GPIO.0-Pad14)") (class "Default")
      (node (ref "U2") (pin "14") (pinfunction "GPIO.0_14") (pintype "passive"))
    )
    (net (code "121") (name "unconnected-(U2-GPIO.1-Pad13)") (class "Default")
      (node (ref "U2") (pin "13") (pinfunction "GPIO.1_13") (pintype "passive"))
    )
    (net (code "122") (name "unconnected-(U2-GPIO.2-Pad12)") (class "Default")
      (node (ref "U2") (pin "12") (pinfunction "GPIO.2_12") (pintype "passive"))
    )
    (net (code "123") (name "unconnected-(U2-GPIO.3-Pad11)") (class "Default")
      (node (ref "U2") (pin "11") (pinfunction "GPIO.3_11") (pintype "passive"))
    )
    (net (code "124") (name "unconnected-(U2-NC-Pad10)") (class "Default")
      (node (ref "U2") (pin "10") (pinfunction "NC_10") (pintype "passive"))
    )
    (net (code "125") (name "unconnected-(U2-RI-Pad1)") (class "Default")
      (node (ref "U2") (pin "1") (pinfunction "RI_1") (pintype "passive+no_connect"))
    )
    (net (code "126") (name "unconnected-(U2-RTS-Pad19)") (class "Default")
      (node (ref "U2") (pin "19") (pinfunction "RTS_19") (pintype "passive"))
    )
    (net (code "127") (name "unconnected-(U2-SUSPEND-Pad17)") (class "Default")
      (node (ref "U2") (pin "17") (pinfunction "SUSPEND_17") (pintype "passive"))
    )
    (net (code "128") (name "unconnected-(U2-VPP-Pad16)") (class "Default")
      (node (ref "U2") (pin "16") (pinfunction "VPP_16") (pintype "passive"))
    )
    (net (code "129") (name "unconnected-(U2-~{RST}-Pad9)") (class "Default")
      (node (ref "U2") (pin "9") (pinfunction "~{RST}_9") (pintype "passive"))
    )
    (net (code "130") (name "unconnected-(U2-~{SUSPEND}-Pad15)") (class "Default")
      (node (ref "U2") (pin "15") (pinfunction "~{SUSPEND}_15") (pintype "passive"))
    )
    (net (code "131") (name "unconnected-(U3-NC-Pad3)") (class "Default")
      (node (ref "U3") (pin "3") (pinfunction "NC_3") (pintype "passive+no_connect"))
    )
    (net (code "132") (name "unconnected-(U6-GPIO_2{slash}P0.14-Pad2)") (class "Default")
      (node (ref "U6") (pin "2") (pinfunction "GPIO_2/P0.14_2") (pintype "bidirectional"))
    )
    (net (code "133") (name "unconnected-(U6-GPIO_3{slash}P0.15-Pad3)") (class "Default")
      (node (ref "U6") (pin "3") (pinfunction "GPIO_3/P0.15_3") (pintype "bidirectional"))
    )
    (net (code "134") (name "unconnected-(U6-GPIO_4{slash}P0.16-Pad4)") (class "Default")
      (node (ref "U6") (pin "4") (pinfunction "GPIO_4/P0.16_4") (pintype "bidirectional"))
    )
    (net (code "135") (name "unconnected-(U6-GPIO_5{slash}P0.24-Pad5)") (class "Default")
      (node (ref "U6") (pin "5") (pinfunction "GPIO_5/P0.24_5") (pintype "bidirectional"))
    )
    (net (code "136") (name "unconnected-(U6-GPIO_7{slash}P0.25-Pad7)") (class "Default")
      (node (ref "U6") (pin "7") (pinfunction "GPIO_7/P0.25_7") (pintype "bidirectional"))
    )
    (net (code "137") (name "unconnected-(U6-GPIO_8{slash}P1.00{slash}TRACE_D0{slash}SWO-Pad8)") (class "Default")
      (node (ref "U6") (pin "8") (pinfunction "GPIO_8/P1.00/TRACE_D0/SWO_8") (pintype "bidirectional"))
    )
    (net (code "138") (name "unconnected-(U6-GPIO_16{slash}P0.03-Pad16)") (class "Default")
      (node (ref "U6") (pin "16") (pinfunction "GPIO_16/P0.03_16") (pintype "bidirectional"))
    )
    (net (code "139") (name "unconnected-(U6-GPIO_17{slash}P0.28-Pad17)") (class "Default")
      (node (ref "U6") (pin "17") (pinfunction "GPIO_17/P0.28_17") (pintype "bidirectional"))
    )
    (net (code "140") (name "unconnected-(U6-GPIO_18{slash}P0.02-Pad18)") (class "Default")
      (node (ref "U6") (pin "18") (pinfunction "GPIO_18/P0.02_18") (pintype "bidirectional"))
    )
    (net (code "141") (name "unconnected-(U6-GPIO_20{slash}P0.31-Pad20)") (class "Default")
      (node (ref "U6") (pin "20") (pinfunction "GPIO_20/P0.31_20") (pintype "bidirectional"))
    )
    (net (code "142") (name "unconnected-(U6-GPIO_21{slash}P1.12-Pad21)") (class "Default")
      (node (ref "U6") (pin "21") (pinfunction "GPIO_21/P1.12_21") (pintype "bidirectional"))
    )
    (net (code "143") (name "unconnected-(U6-GPIO_22{slash}P1.13-Pad22)") (class "Default")
      (node (ref "U6") (pin "22") (pinfunction "GPIO_22/P1.13_22") (pintype "bidirectional"))
    )
    (net (code "144") (name "unconnected-(U6-GPIO_23{slash}P0.29-Pad23)") (class "Default")
      (node (ref "U6") (pin "23") (pinfunction "GPIO_23/P0.29_23") (pintype "bidirectional"))
    )
    (net (code "145") (name "unconnected-(U6-GPIO_24{slash}P0.30-Pad24)") (class "Default")
      (node (ref "U6") (pin "24") (pinfunction "GPIO_24/P0.30_24") (pintype "bidirectional"))
    )
    (net (code "146") (name "unconnected-(U6-GPIO_25{slash}P0.04-Pad25)") (class "Default")
      (node (ref "U6") (pin "25") (pinfunction "GPIO_25/P0.04_25") (pintype "bidirectional"))
    )
    (net (code "147") (name "unconnected-(U6-GPIO_27{slash}P0.05-Pad27)") (class "Default")
      (node (ref "U6") (pin "27") (pinfunction "GPIO_27/P0.05_27") (pintype "bidirectional"))
    )
    (net (code "148") (name "unconnected-(U6-GPIO_28{slash}P0.09{slash}NFC1-Pad28)") (class "Default")
      (node (ref "U6") (pin "28") (pinfunction "GPIO_28/P0.09/NFC1_28") (pintype "bidirectional"))
    )
    (net (code "149") (name "unconnected-(U6-GPIO_29{slash}P0.10{slash}NFC2-Pad29)") (class "Default")
      (node (ref "U6") (pin "29") (pinfunction "GPIO_29/P0.10/NFC2_29") (pintype "bidirectional"))
    )
    (net (code "150") (name "unconnected-(U6-GPIO_32{slash}P0.11{slash}TRACE_D2-Pad32)") (class "Default")
      (node (ref "U6") (pin "32") (pinfunction "GPIO_32/P0.11/TRACE_D2_32") (pintype "bidirectional"))
    )
    (net (code "151") (name "unconnected-(U6-GPIO_34{slash}P1.08-Pad34)") (class "Default")
      (node (ref "U6") (pin "34") (pinfunction "GPIO_34/P1.08_34") (pintype "bidirectional"))
    )
    (net (code "152") (name "unconnected-(U6-GPIO_35{slash}P1.01-Pad35)") (class "Default")
      (node (ref "U6") (pin "35") (pinfunction "GPIO_35/P1.01_35") (pintype "bidirectional"))
    )
    (net (code "153") (name "unconnected-(U6-GPIO_36{slash}P1.02-Pad36)") (class "Default")
      (node (ref "U6") (pin "36") (pinfunction "GPIO_36/P1.02_36") (pintype "bidirectional"))
    )
    (net (code "154") (name "unconnected-(U6-GPIO_39{slash}P1.11-Pad39)") (class "Default")
      (node (ref "U6") (pin "39") (pinfunction "GPIO_39/P1.11_39") (pintype "bidirectional"))
    )
    (net (code "155") (name "unconnected-(U6-GPIO_40{slash}P1.15-Pad40)") (class "Default")
      (node (ref "U6") (pin "40") (pinfunction "GPIO_40/P1.15_40") (pintype "bidirectional"))
    )
    (net (code "156") (name "unconnected-(U6-GPIO_41{slash}P1.14-Pad41)") (class "Default")
      (node (ref "U6") (pin "41") (pinfunction "GPIO_41/P1.14_41") (pintype "bidirectional"))
    )
    (net (code "157") (name "unconnected-(U6-GPIO_42{slash}P0.26-Pad42)") (class "Default")
      (node (ref "U6") (pin "42") (pinfunction "GPIO_42/P0.26_42") (pintype "bidirectional"))
    )
    (net (code "158") (name "unconnected-(U6-GPIO_43{slash}P0.06-Pad43)") (class "Default")
      (node (ref "U6") (pin "43") (pinfunction "GPIO_43/P0.06_43") (pintype "bidirectional"))
    )
    (net (code "159") (name "unconnected-(U6-GPIO_44{slash}P0.27-Pad44)") (class "Default")
      (node (ref "U6") (pin "44") (pinfunction "GPIO_44/P0.27_44") (pintype "bidirectional"))
    )
    (net (code "160") (name "unconnected-(U6-GPIO_45{slash}P0.07{slash}TRACE_CLK-Pad45)") (class "Default")
      (node (ref "U6") (pin "45") (pinfunction "GPIO_45/P0.07/TRACE_CLK_45") (pintype "bidirectional"))
    )
    (net (code "161") (name "unconnected-(U6-GPIO_46{slash}P0.12{slash}TRACE_D1-Pad46)") (class "Default")
      (node (ref "U6") (pin "46") (pinfunction "GPIO_46/P0.12/TRACE_D1_46") (pintype "bidirectional"))
    )
    (net (code "162") (name "unconnected-(U6-RSVD13-Pad13)") (class "Default")
      (node (ref "U6") (pin "13") (pinfunction "RSVD13_13") (pintype "passive"))
    )
    (net (code "163") (name "unconnected-(USB1-CC1-PadA5)") (class "Default")
      (node (ref "USB1") (pin "A5") (pinfunction "CC1_A5") (pintype "passive+no_connect"))
    )
    (net (code "164") (name "unconnected-(USB1-CC2-PadB5)") (class "Default")
      (node (ref "USB1") (pin "B5") (pinfunction "CC2_B5") (pintype "passive+no_connect"))
    )
    (net (code "165") (name "unconnected-(USB1-SBU1-PadA8)") (class "Default")
      (node (ref "USB1") (pin "A8") (pinfunction "SBU1_A8") (pintype "passive+no_connect"))
    )
    (net (code "166") (name "unconnected-(USB1-SBU2-PadB8)") (class "Default")
      (node (ref "USB1") (pin "B8") (pinfunction "SBU2_B8") (pintype "passive+no_connect"))
    )
  )
)
